# usb-isolator.net
KiCad netlist of a schematic drawn in EAGLE
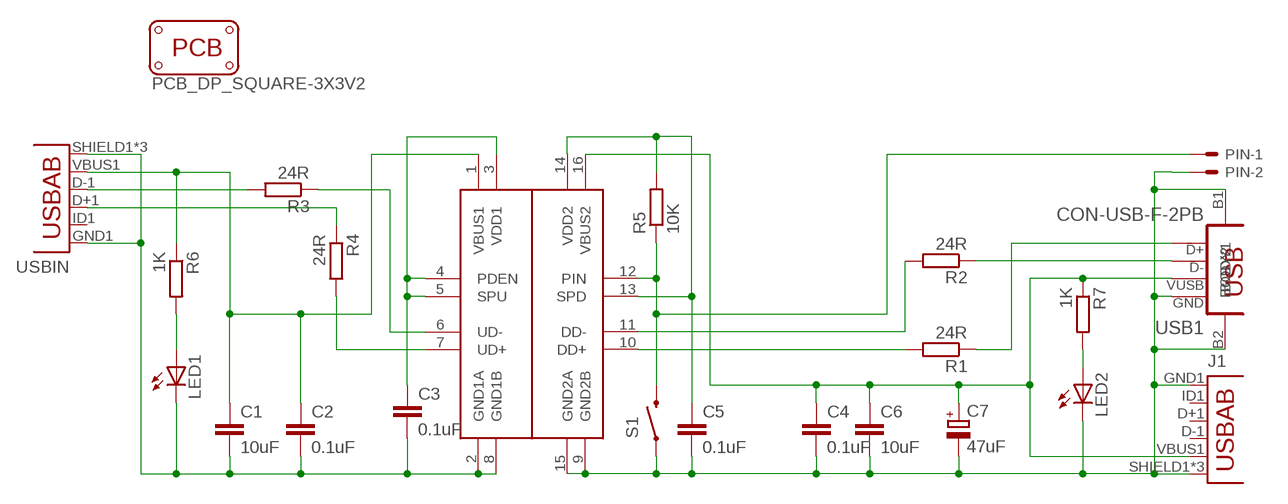
[diagram p0: schematic, sheet 1]

(export (version "E")
  (design (tool "Eeschema 10.0.6"))
  (components
    (comp (ref "C1")
      (value "10uF")
      (footprint "eagle-import:C0805K")
      (libsource (lib "eagle-import") (part "C-EUC0805K"))
    )
    (comp (ref "C2")
      (value "0.1uF")
      (footprint "eagle-import:C0603K")
      (libsource (lib "eagle-import") (part "C-EUC0603K"))
    )
    (comp (ref "C3")
      (value "0.1uF")
      (footprint "eagle-import:C0603K")
      (libsource (lib "eagle-import") (part "C-EUC0603K"))
    )
    (comp (ref "C4")
      (value "0.1uF")
      (footprint "eagle-import:C0603K")
      (libsource (lib "eagle-import") (part "C-EUC0603K"))
    )
    (comp (ref "C5")
      (value "0.1uF")
      (footprint "eagle-import:C0603K")
      (libsource (lib "eagle-import") (part "C-EUC0603K"))
    )
    (comp (ref "C6")
      (value "10uF")
      (footprint "eagle-import:C0805K")
      (libsource (lib "eagle-import") (part "C-EUC0805K"))
    )
    (comp (ref "C7")
      (value "47uF")
      (footprint "eagle-import:D_7343-31W")
      (libsource (lib "eagle-import") (part "CPOL-EUD/7343-31W"))
    )
    (comp (ref "IC1")
      (value "ADUM3160BRWZ")
      (footprint "eagle-import:SO16W")
      (libsource (lib "eagle-import") (part "ADUM3160BRWZ"))
    )
    (comp (ref "J1")
      (value "USB-ABCONN-11794")
      (footprint "eagle-import:USB-AB-MICRO-SMD_V03")
      (libsource (lib "eagle-import") (part "USB-ABCONN-11794"))
    )
    (comp (ref "LED1")
      (value "LED-0805")
      (footprint "eagle-import:LED-805")
      (libsource (lib "eagle-import") (part "LED-0805"))
    )
    (comp (ref "LED2")
      (value "LED-0805")
      (footprint "eagle-import:LED-805")
      (libsource (lib "eagle-import") (part "LED-0805"))
    )
    (comp (ref "PIN")
      (value "22-23-2021")
      (footprint "eagle-import:22-23-2021")
      (fields (field (name "MF") "MOLEX"))
      (libsource (lib "eagle-import") (part "22-23-2021"))
    )
    (comp (ref "R1")
      (value "24R")
      (footprint "eagle-import:R0603")
      (libsource (lib "eagle-import") (part "R-EU_R0603"))
    )
    (comp (ref "R2")
      (value "24R")
      (footprint "eagle-import:R0603")
      (libsource (lib "eagle-import") (part "R-EU_R0603"))
    )
    (comp (ref "R3")
      (value "24R")
      (footprint "eagle-import:R0603")
      (libsource (lib "eagle-import") (part "R-EU_R0603"))
    )
    (comp (ref "R4")
      (value "24R")
      (footprint "eagle-import:R0603")
      (libsource (lib "eagle-import") (part "R-EU_R0603"))
    )
    (comp (ref "R5")
      (value "10K")
      (footprint "eagle-import:R0603")
      (libsource (lib "eagle-import") (part "R-EU_R0603"))
    )
    (comp (ref "R6")
      (value "1K")
      (footprint "eagle-import:R0603")
      (libsource (lib "eagle-import") (part "R-EU_R0603"))
    )
    (comp (ref "R7")
      (value "1K")
      (footprint "eagle-import:R0603")
      (libsource (lib "eagle-import") (part "R-EU_R0603"))
    )
    (comp (ref "S1")
      (value "SWITCH-MOMENTARY-2SMD-1101NE")
      (footprint "eagle-import:TACTILE-SWITCH-1101NE")
      (libsource (lib "eagle-import") (part "SWITCH-MOMENTARY-2SMD-1101NE"))
    )
    (comp (ref "USB-ISOLATOR")
      (value "PCB_DP_SQUARE-3X3V2")
      (footprint "eagle-import:DP3030_V2")
      (libsource (lib "eagle-import") (part "PCB_DP_SQUARE-3X3V2"))
    )
    (comp (ref "USB1")
      (value "CON-USB-F-2PB")
      (footprint "eagle-import:CONN_USB_A_F")
      (libsource (lib "eagle-import") (part "CON-USB-F-2PB"))
    )
    (comp (ref "USBIN")
      (value "USB-ABCONN-11794")
      (footprint "eagle-import:USB-AB-MICRO-SMD_V03")
      (libsource (lib "eagle-import") (part "USB-ABCONN-11794"))
    )
  )
  (nets
    (net (code "1") (name "Net-(IC1-DD+)") (class "Default")
      (node (ref "IC1") (pin "10") (pinfunction "DD+_10") (pintype "bidirectional"))
      (node (ref "R1") (pin "2") (pinfunction "2_2") (pintype "passive"))
    )
    (net (code "2") (name "Net-(IC1-DD-)") (class "Default")
      (node (ref "IC1") (pin "11") (pinfunction "DD-_11") (pintype "bidirectional"))
      (node (ref "R2") (pin "2") (pinfunction "2_2") (pintype "passive"))
    )
    (net (code "3") (name "Net-(IC1-GND1A)") (class "Default")
      (node (ref "C1") (pin "2") (pinfunction "2_2") (pintype "passive"))
      (node (ref "C2") (pin "2") (pinfunction "2_2") (pintype "passive"))
      (node (ref "C3") (pin "2") (pinfunction "2_2") (pintype "passive"))
      (node (ref "IC1") (pin "2") (pinfunction "GND1A_2") (pintype "power_in"))
      (node (ref "IC1") (pin "8") (pinfunction "GND1B_8") (pintype "power_in"))
      (node (ref "LED1") (pin "C") (pinfunction "C_C") (pintype "passive"))
      (node (ref "USBIN") (pin "GND1") (pinfunction "GND_GND1") (pintype "bidirectional"))
      (node (ref "USBIN") (pin "SHIELD1") (pinfunction "SHIELD_SHIELD1") (pintype "bidirectional"))
      (node (ref "USBIN") (pin "SHIELD2") (pinfunction "SHIELD_SHIELD2") (pintype "bidirectional"))
      (node (ref "USBIN") (pin "SHIELD3") (pinfunction "SHIELD_SHIELD3") (pintype "bidirectional"))
    )
    (net (code "4") (name "Net-(IC1-GND2A)") (class "Default")
      (node (ref "C4") (pin "2") (pinfunction "2_2") (pintype "passive"))
      (node (ref "C5") (pin "2") (pinfunction "2_2") (pintype "passive"))
      (node (ref "C6") (pin "2") (pinfunction "2_2") (pintype "passive"))
      (node (ref "C7") (pin "-") (pinfunction "-_-") (pintype "passive"))
      (node (ref "IC1") (pin "15") (pinfunction "GND2A_15") (pintype "power_in"))
      (node (ref "IC1") (pin "9") (pinfunction "GND2B_9") (pintype "power_in"))
      (node (ref "J1") (pin "GND1") (pinfunction "GND_GND1") (pintype "bidirectional"))
      (node (ref "J1") (pin "SHIELD1") (pinfunction "SHIELD_SHIELD1") (pintype "bidirectional"))
      (node (ref "J1") (pin "SHIELD2") (pinfunction "SHIELD_SHIELD2") (pintype "bidirectional"))
      (node (ref "J1") (pin "SHIELD3") (pinfunction "SHIELD_SHIELD3") (pintype "bidirectional"))
      (node (ref "LED2") (pin "C") (pinfunction "C_C") (pintype "passive"))
      (node (ref "PIN") (pin "2") (pinfunction "S_2") (pintype "passive"))
      (node (ref "S1") (pin "1") (pinfunction "1_1") (pintype "passive"))
      (node (ref "USB1") (pin "4") (pinfunction "GND_4") (pintype "bidirectional"))
      (node (ref "USB1") (pin "B1") (pinfunction "BODY1_B1") (pintype "bidirectional"))
      (node (ref "USB1") (pin "B2") (pinfunction "BODY2_B2") (pintype "bidirectional"))
    )
    (net (code "5") (name "Net-(IC1-PDEN)") (class "Default")
      (node (ref "C3") (pin "1") (pinfunction "1_1") (pintype "passive"))
      (node (ref "IC1") (pin "3") (pinfunction "VDD1_3") (pintype "power_in"))
      (node (ref "IC1") (pin "4") (pinfunction "PDEN_4") (pintype "input"))
      (node (ref "IC1") (pin "5") (pinfunction "SPU_5") (pintype "input"))
    )
    (net (code "6") (name "Net-(IC1-PIN)") (class "Default")
      (node (ref "IC1") (pin "12") (pinfunction "PIN_12") (pintype "input"))
      (node (ref "PIN") (pin "1") (pinfunction "S_1") (pintype "passive"))
      (node (ref "R5") (pin "1") (pinfunction "1_1") (pintype "passive"))
      (node (ref "S1") (pin "2") (pinfunction "2_2") (pintype "passive"))
    )
    (net (code "7") (name "Net-(IC1-SPD)") (class "Default")
      (node (ref "C5") (pin "1") (pinfunction "1_1") (pintype "passive"))
      (node (ref "IC1") (pin "13") (pinfunction "SPD_13") (pintype "input"))
      (node (ref "IC1") (pin "14") (pinfunction "VDD2_14") (pintype "bidirectional"))
      (node (ref "R5") (pin "2") (pinfunction "2_2") (pintype "passive"))
    )
    (net (code "8") (name "Net-(IC1-UD+)") (class "Default")
      (node (ref "IC1") (pin "7") (pinfunction "UD+_7") (pintype "bidirectional"))
      (node (ref "R4") (pin "2") (pinfunction "2_2") (pintype "passive"))
    )
    (net (code "9") (name "Net-(IC1-UD-)") (class "Default")
      (node (ref "IC1") (pin "6") (pinfunction "UD-_6") (pintype "bidirectional"))
      (node (ref "R3") (pin "1") (pinfunction "1_1") (pintype "passive"))
    )
    (net (code "10") (name "Net-(IC1-VBUS1)") (class "Default")
      (node (ref "C1") (pin "1") (pinfunction "1_1") (pintype "passive"))
      (node (ref "C2") (pin "1") (pinfunction "1_1") (pintype "passive"))
      (node (ref "IC1") (pin "1") (pinfunction "VBUS1_1") (pintype "power_in"))
      (node (ref "R6") (pin "1") (pinfunction "1_1") (pintype "passive"))
      (node (ref "USBIN") (pin "VBUS1") (pinfunction "VBUS_VBUS1") (pintype "bidirectional"))
    )
    (net (code "11") (name "Net-(IC1-VBUS2)") (class "Default")
      (node (ref "C4") (pin "1") (pinfunction "1_1") (pintype "passive"))
      (node (ref "C6") (pin "1") (pinfunction "1_1") (pintype "passive"))
      (node (ref "C7") (pin "+") (pinfunction "+_+") (pintype "passive"))
      (node (ref "IC1") (pin "16") (pinfunction "VBUS2_16") (pintype "bidirectional"))
      (node (ref "J1") (pin "VBUS1") (pinfunction "VBUS_VBUS1") (pintype "bidirectional"))
      (node (ref "R7") (pin "1") (pinfunction "1_1") (pintype "passive"))
      (node (ref "USB1") (pin "1") (pinfunction "VUSB_1") (pintype "bidirectional"))
    )
    (net (code "12") (name "Net-(LED1-PadA)") (class "Default")
      (node (ref "LED1") (pin "A") (pinfunction "A_A") (pintype "passive"))
      (node (ref "R6") (pin "2") (pinfunction "2_2") (pintype "passive"))
    )
    (net (code "13") (name "Net-(LED2-PadA)") (class "Default")
      (node (ref "LED2") (pin "A") (pinfunction "A_A") (pintype "passive"))
      (node (ref "R7") (pin "2") (pinfunction "2_2") (pintype "passive"))
    )
    (net (code "14") (name "Net-(USB1-D+)") (class "Default")
      (node (ref "R1") (pin "1") (pinfunction "1_1") (pintype "passive"))
      (node (ref "USB1") (pin "3") (pinfunction "D+_3") (pintype "bidirectional"))
    )
    (net (code "15") (name "Net-(USB1-D-)") (class "Default")
      (node (ref "R2") (pin "1") (pinfunction "1_1") (pintype "passive"))
      (node (ref "USB1") (pin "2") (pinfunction "D-_2") (pintype "bidirectional"))
    )
    (net (code "16") (name "Net-(USBIN-D+)") (class "Default")
      (node (ref "R4") (pin "1") (pinfunction "1_1") (pintype "passive"))
      (node (ref "USBIN") (pin "D+1") (pinfunction "D+_D+1") (pintype "bidirectional"))
    )
    (net (code "17") (name "Net-(USBIN-D-)") (class "Default")
      (node (ref "R3") (pin "2") (pinfunction "2_2") (pintype "passive"))
      (node (ref "USBIN") (pin "D-1") (pinfunction "D-_D-1") (pintype "bidirectional"))
    )
    (net (code "18") (name "unconnected-(J1-D+-PadD+1)") (class "Default")
      (node (ref "J1") (pin "D+1") (pinfunction "D+_D+1") (pintype "bidirectional"))
    )
    (net (code "19") (name "unconnected-(J1-D--PadD-1)") (class "Default")
      (node (ref "J1") (pin "D-1") (pinfunction "D-_D-1") (pintype "bidirectional"))
    )
    (net (code "20") (name "unconnected-(J1-USBID-PadID1)") (class "Default")
      (node (ref "J1") (pin "ID1") (pinfunction "USBID_ID1") (pintype "bidirectional"))
    )
    (net (code "21") (name "unconnected-(USBIN-USBID-PadID1)") (class "Default")
      (node (ref "USBIN") (pin "ID1") (pinfunction "USBID_ID1") (pintype "bidirectional"))
    )
  )
)
